# coreV_01.net
KiCad netlist of a schematic drawn in EAGLE
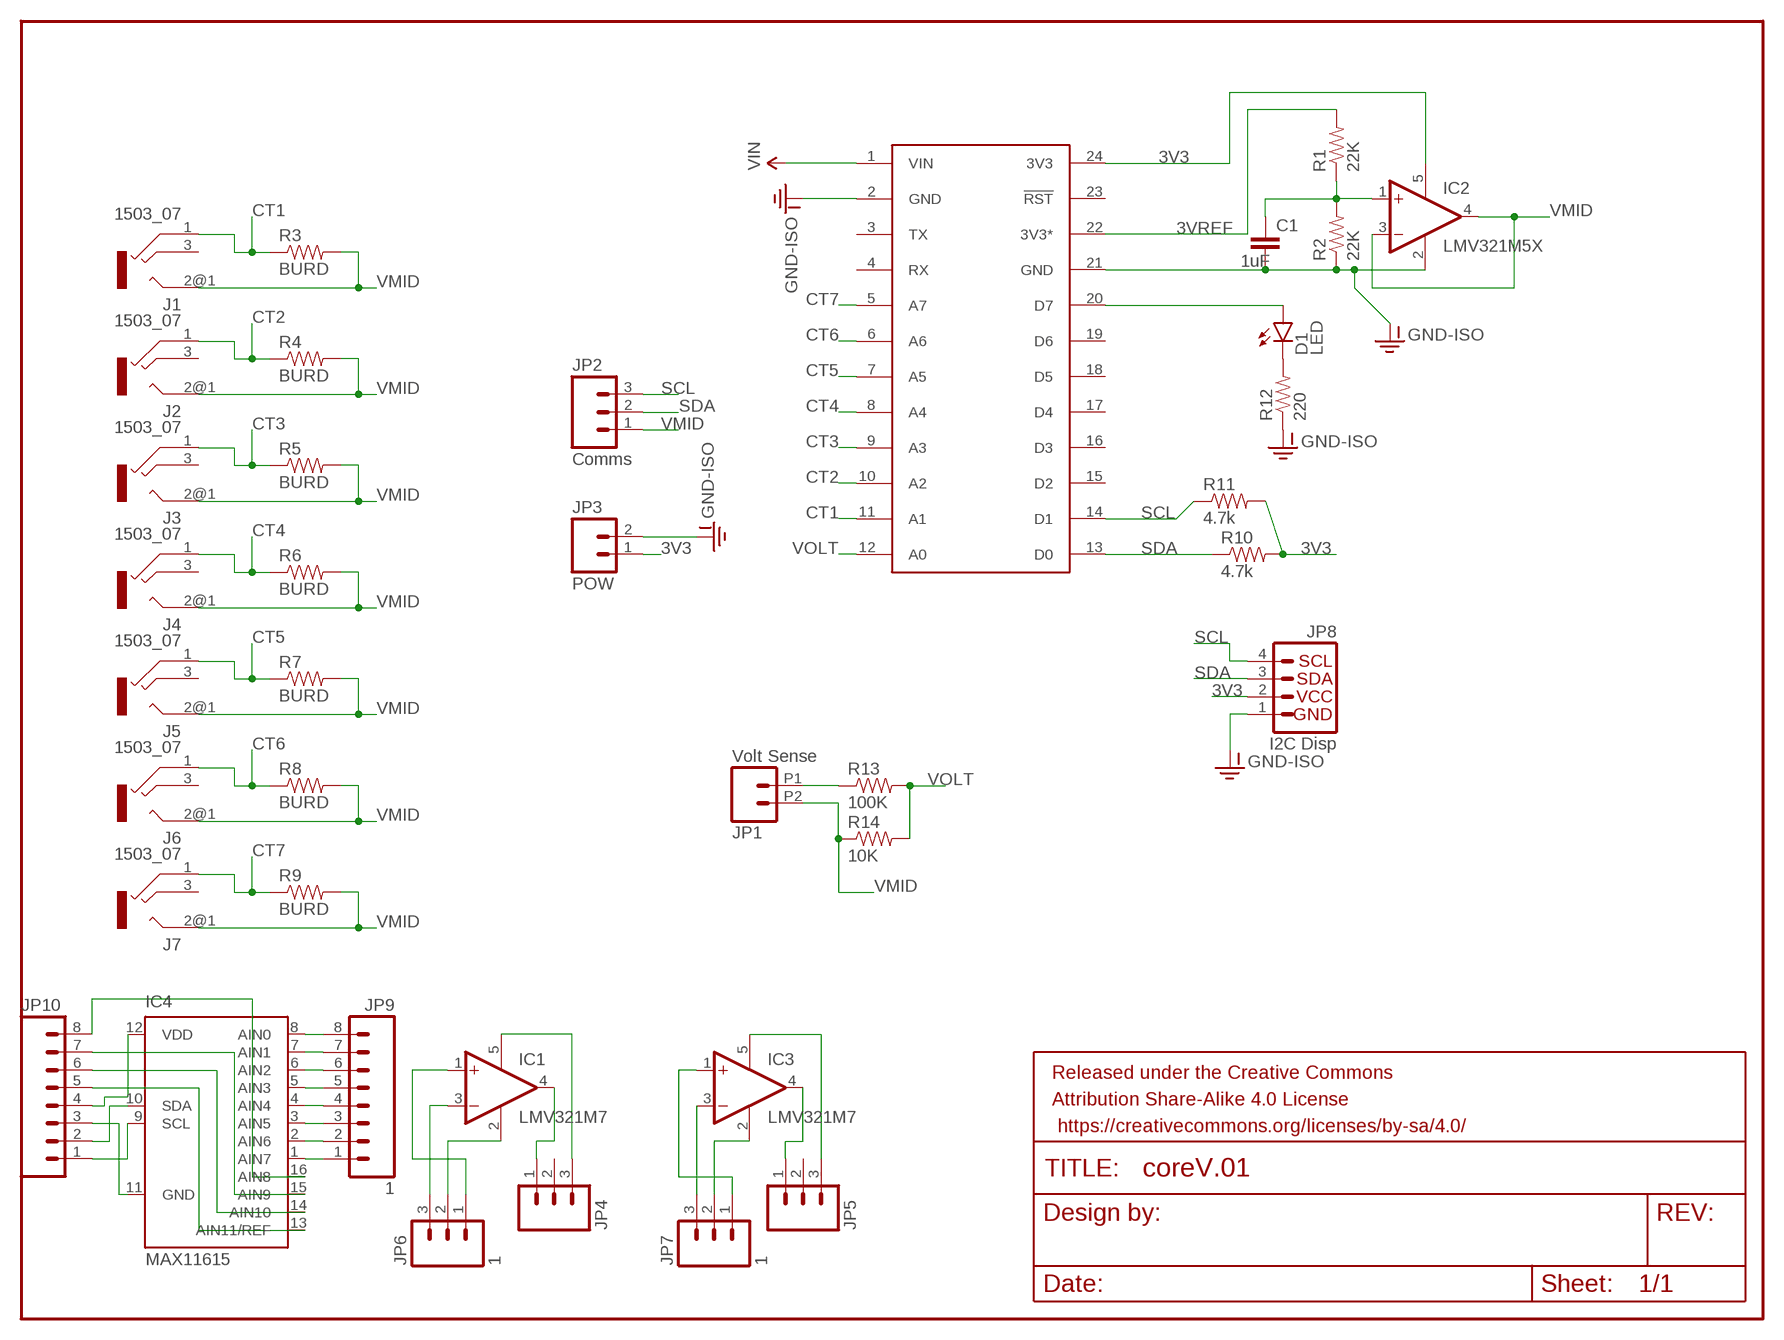
[diagram p0: schematic, sheet 1]

(export (version "E")
  (design (tool "Eeschema 10.0.6"))
  (components
    (comp (ref "C1")
      (value "1uF")
      (footprint "eagle-import:CAP-PTH-SMALL")
      (libsource (lib "eagle-import") (part "CAPPTH"))
    )
    (comp (ref "D1")
      (value "LED")
      (footprint "eagle-import:LED3MM")
      (libsource (lib "eagle-import") (part "LED3MM"))
    )
    (comp (ref "FRAME1")
      (value "emonCore")
      (footprint "eagle-import:CREATIVE_COMMONS")
      (fields (field (name "DESIGNER") "NAME"))
      (libsource (lib "eagle-import") (part "FRAME-LETTER"))
    )
    (comp (ref "IC1")
      (value "LMV321M7")
      (footprint "eagle-import:SC70-5L")
      (libsource (lib "eagle-import") (part "LMV321?M7"))
    )
    (comp (ref "IC2")
      (value "LMV321M5X")
      (footprint "eagle-import:SOT23-5")
      (libsource (lib "eagle-import") (part "LMV321?M5X"))
    )
    (comp (ref "IC3")
      (value "LMV321M7")
      (footprint "eagle-import:SC70-5L")
      (libsource (lib "eagle-import") (part "LMV321?M7"))
    )
    (comp (ref "IC4")
      (value "MAX11615")
      (footprint "eagle-import:QSOP16")
      (fields (field (name "MF") "MAXIM") (field (name "MPN") "MAX1039AEEE+"))
      (libsource (lib "eagle-import") (part "MAX1039"))
    )
    (comp (ref "J1")
      (value "1503_07")
      (footprint "eagle-import:1503_07")
      (libsource (lib "eagle-import") (part "1503_?07"))
    )
    (comp (ref "J2")
      (value "1503_07")
      (footprint "eagle-import:1503_07")
      (libsource (lib "eagle-import") (part "1503_?07"))
    )
    (comp (ref "J3")
      (value "1503_07")
      (footprint "eagle-import:1503_07")
      (libsource (lib "eagle-import") (part "1503_?07"))
    )
    (comp (ref "J4")
      (value "1503_07")
      (footprint "eagle-import:1503_07")
      (libsource (lib "eagle-import") (part "1503_?07"))
    )
    (comp (ref "J5")
      (value "1503_07")
      (footprint "eagle-import:1503_07")
      (libsource (lib "eagle-import") (part "1503_?07"))
    )
    (comp (ref "J6")
      (value "1503_07")
      (footprint "eagle-import:1503_07")
      (libsource (lib "eagle-import") (part "1503_?07"))
    )
    (comp (ref "J7")
      (value "1503_07")
      (footprint "eagle-import:1503_07")
      (libsource (lib "eagle-import") (part "1503_?07"))
    )
    (comp (ref "JP1")
      (value "Volt Sense")
      (footprint "eagle-import:1X02_2.54_SCREWTERM")
      (libsource (lib "eagle-import") (part "M022.54MM_SCREWTERM"))
    )
    (comp (ref "JP2")
      (value "Comms")
      (footprint "eagle-import:1X03")
      (libsource (lib "eagle-import") (part "M03PTH"))
    )
    (comp (ref "JP3")
      (value "POW")
      (footprint "eagle-import:1X02")
      (libsource (lib "eagle-import") (part "M02PTH"))
    )
    (comp (ref "JP4")
      (value "M03PTH")
      (footprint "eagle-import:1X03")
      (libsource (lib "eagle-import") (part "M03PTH"))
    )
    (comp (ref "JP5")
      (value "M03PTH")
      (footprint "eagle-import:1X03")
      (libsource (lib "eagle-import") (part "M03PTH"))
    )
    (comp (ref "JP6")
      (value "1")
      (footprint "eagle-import:1X03")
      (libsource (lib "eagle-import") (part "M03PTH"))
    )
    (comp (ref "JP7")
      (value "1")
      (footprint "eagle-import:1X03")
      (libsource (lib "eagle-import") (part "M03PTH"))
    )
    (comp (ref "JP8")
      (value "I2C Disp")
      (footprint "eagle-import:1X04")
      (libsource (lib "eagle-import") (part "I2C_STANDARD"))
    )
    (comp (ref "JP9")
      (value "1")
      (footprint "eagle-import:1X08")
      (libsource (lib "eagle-import") (part "M08SILK_FEMALE_PTH"))
    )
    (comp (ref "JP10")
      (value "M08SILK_FEMALE_PTH")
      (footprint "eagle-import:1X08")
      (libsource (lib "eagle-import") (part "M08SILK_FEMALE_PTH"))
    )
    (comp (ref "R1")
      (value "22K")
      (footprint "eagle-import:AXIAL-0.3")
      (libsource (lib "eagle-import") (part "RESISTORAXIAL-0.3"))
    )
    (comp (ref "R2")
      (value "22K")
      (footprint "eagle-import:AXIAL-0.3")
      (libsource (lib "eagle-import") (part "RESISTORAXIAL-0.3"))
    )
    (comp (ref "R3")
      (value "BURD")
      (footprint "eagle-import:AXIAL-0.3")
      (libsource (lib "eagle-import") (part "RESISTORAXIAL-0.3"))
    )
    (comp (ref "R4")
      (value "BURD")
      (footprint "eagle-import:AXIAL-0.3")
      (libsource (lib "eagle-import") (part "RESISTORAXIAL-0.3"))
    )
    (comp (ref "R5")
      (value "BURD")
      (footprint "eagle-import:AXIAL-0.3")
      (libsource (lib "eagle-import") (part "RESISTORAXIAL-0.3"))
    )
    (comp (ref "R6")
      (value "BURD")
      (footprint "eagle-import:AXIAL-0.3")
      (libsource (lib "eagle-import") (part "RESISTORAXIAL-0.3"))
    )
    (comp (ref "R7")
      (value "BURD")
      (footprint "eagle-import:AXIAL-0.3")
      (libsource (lib "eagle-import") (part "RESISTORAXIAL-0.3"))
    )
    (comp (ref "R8")
      (value "BURD")
      (footprint "eagle-import:AXIAL-0.3")
      (libsource (lib "eagle-import") (part "RESISTORAXIAL-0.3"))
    )
    (comp (ref "R9")
      (value "BURD")
      (footprint "eagle-import:AXIAL-0.3")
      (libsource (lib "eagle-import") (part "RESISTORAXIAL-0.3"))
    )
    (comp (ref "R10")
      (value "4.7k")
      (footprint "eagle-import:AXIAL-0.3")
      (libsource (lib "eagle-import") (part "RESISTORAXIAL-0.3"))
    )
    (comp (ref "R11")
      (value "4.7k")
      (footprint "eagle-import:AXIAL-0.3")
      (libsource (lib "eagle-import") (part "RESISTORAXIAL-0.3"))
    )
    (comp (ref "R12")
      (value "220")
      (footprint "eagle-import:AXIAL-0.3")
      (libsource (lib "eagle-import") (part "RESISTORAXIAL-0.3"))
    )
    (comp (ref "R13")
      (value "100K")
      (footprint "eagle-import:AXIAL-0.3")
      (libsource (lib "eagle-import") (part "RESISTORAXIAL-0.3"))
    )
    (comp (ref "R14")
      (value "10K")
      (footprint "eagle-import:AXIAL-0.3")
      (libsource (lib "eagle-import") (part "RESISTORAXIAL-0.3"))
    )
    (comp (ref "U$1")
      (value "SPARK_CORE")
      (footprint "eagle-import:SPARK_CORE")
      (libsource (lib "eagle-import") (part "SPARK_CORECORE"))
    )
  )
  (nets
    (net (code "1") (name "/3V3") (class "Default")
      (node (ref "IC2") (pin "5") (pinfunction "V+_5") (pintype "power_in"))
      (node (ref "JP3") (pin "1") (pinfunction "1_1") (pintype "passive"))
      (node (ref "JP8") (pin "2") (pinfunction "2_2") (pintype "passive"))
      (node (ref "R10") (pin "P$2") (pinfunction "2_P$2") (pintype "passive"))
      (node (ref "R11") (pin "P$2") (pinfunction "2_P$2") (pintype "passive"))
      (node (ref "U$1") (pin "24") (pinfunction "3V3_24") (pintype "power_in"))
    )
    (net (code "2") (name "/3VREF") (class "Default")
      (node (ref "R1") (pin "P$2") (pinfunction "2_P$2") (pintype "passive"))
      (node (ref "U$1") (pin "22") (pinfunction "3V3*_22") (pintype "power_in"))
    )
    (net (code "3") (name "/CT1") (class "Default")
      (node (ref "J1") (pin "1") (pinfunction "1_1") (pintype "passive"))
      (node (ref "R3") (pin "P$1") (pinfunction "1_P$1") (pintype "passive"))
      (node (ref "U$1") (pin "11") (pinfunction "A1_11") (pintype "bidirectional"))
    )
    (net (code "4") (name "/CT2") (class "Default")
      (node (ref "J2") (pin "1") (pinfunction "1_1") (pintype "passive"))
      (node (ref "R4") (pin "P$1") (pinfunction "1_P$1") (pintype "passive"))
      (node (ref "U$1") (pin "10") (pinfunction "A2_10") (pintype "bidirectional"))
    )
    (net (code "5") (name "/CT3") (class "Default")
      (node (ref "J3") (pin "1") (pinfunction "1_1") (pintype "passive"))
      (node (ref "R5") (pin "P$1") (pinfunction "1_P$1") (pintype "passive"))
      (node (ref "U$1") (pin "9") (pinfunction "A3_9") (pintype "bidirectional"))
    )
    (net (code "6") (name "/CT4") (class "Default")
      (node (ref "J4") (pin "1") (pinfunction "1_1") (pintype "passive"))
      (node (ref "R6") (pin "P$1") (pinfunction "1_P$1") (pintype "passive"))
      (node (ref "U$1") (pin "8") (pinfunction "A4_8") (pintype "bidirectional"))
    )
    (net (code "7") (name "/CT5") (class "Default")
      (node (ref "J5") (pin "1") (pinfunction "1_1") (pintype "passive"))
      (node (ref "R7") (pin "P$1") (pinfunction "1_P$1") (pintype "passive"))
      (node (ref "U$1") (pin "7") (pinfunction "A5_7") (pintype "bidirectional"))
    )
    (net (code "8") (name "/CT6") (class "Default")
      (node (ref "J6") (pin "1") (pinfunction "1_1") (pintype "passive"))
      (node (ref "R8") (pin "P$1") (pinfunction "1_P$1") (pintype "passive"))
      (node (ref "U$1") (pin "6") (pinfunction "A6_6") (pintype "bidirectional"))
    )
    (net (code "9") (name "/CT7") (class "Default")
      (node (ref "J7") (pin "1") (pinfunction "1_1") (pintype "passive"))
      (node (ref "R9") (pin "P$1") (pinfunction "1_P$1") (pintype "passive"))
      (node (ref "U$1") (pin "5") (pinfunction "A7_5") (pintype "bidirectional"))
    )
    (net (code "10") (name "/SCL") (class "Default")
      (node (ref "JP2") (pin "3") (pinfunction "3_3") (pintype "passive"))
      (node (ref "JP8") (pin "4") (pinfunction "4_4") (pintype "passive"))
      (node (ref "R11") (pin "P$1") (pinfunction "1_P$1") (pintype "passive"))
      (node (ref "U$1") (pin "14") (pinfunction "D1_14") (pintype "bidirectional"))
    )
    (net (code "11") (name "/SDA") (class "Default")
      (node (ref "JP2") (pin "2") (pinfunction "2_2") (pintype "passive"))
      (node (ref "JP8") (pin "3") (pinfunction "3_3") (pintype "passive"))
      (node (ref "R10") (pin "P$1") (pinfunction "1_P$1") (pintype "passive"))
      (node (ref "U$1") (pin "13") (pinfunction "D0_13") (pintype "bidirectional"))
    )
    (net (code "12") (name "/VMID") (class "Default")
      (node (ref "IC2") (pin "3") (pinfunction "-IN_3") (pintype "input"))
      (node (ref "IC2") (pin "4") (pinfunction "OUT_4") (pintype "output"))
      (node (ref "J1") (pin "2@1") (pinfunction "2_2@1") (pintype "passive"))
      (node (ref "J2") (pin "2@1") (pinfunction "2_2@1") (pintype "passive"))
      (node (ref "J3") (pin "2@1") (pinfunction "2_2@1") (pintype "passive"))
      (node (ref "J4") (pin "2@1") (pinfunction "2_2@1") (pintype "passive"))
      (node (ref "J5") (pin "2@1") (pinfunction "2_2@1") (pintype "passive"))
      (node (ref "J6") (pin "2@1") (pinfunction "2_2@1") (pintype "passive"))
      (node (ref "J7") (pin "2@1") (pinfunction "2_2@1") (pintype "passive"))
      (node (ref "JP1") (pin "P2") (pinfunction "2_P2") (pintype "passive"))
      (node (ref "JP2") (pin "1") (pinfunction "1_1") (pintype "passive"))
      (node (ref "R14") (pin "P$1") (pinfunction "1_P$1") (pintype "passive"))
      (node (ref "R3") (pin "P$2") (pinfunction "2_P$2") (pintype "passive"))
      (node (ref "R4") (pin "P$2") (pinfunction "2_P$2") (pintype "passive"))
      (node (ref "R5") (pin "P$2") (pinfunction "2_P$2") (pintype "passive"))
      (node (ref "R6") (pin "P$2") (pinfunction "2_P$2") (pintype "passive"))
      (node (ref "R7") (pin "P$2") (pinfunction "2_P$2") (pintype "passive"))
      (node (ref "R8") (pin "P$2") (pinfunction "2_P$2") (pintype "passive"))
      (node (ref "R9") (pin "P$2") (pinfunction "2_P$2") (pintype "passive"))
    )
    (net (code "13") (name "/VOLT") (class "Default")
      (node (ref "R13") (pin "P$2") (pinfunction "2_P$2") (pintype "passive"))
      (node (ref "R14") (pin "P$2") (pinfunction "2_P$2") (pintype "passive"))
      (node (ref "U$1") (pin "12") (pinfunction "A0_12") (pintype "bidirectional"))
    )
    (net (code "14") (name "GND-ISO") (class "Default")
      (node (ref "C1") (pin "2") (pinfunction "2_2") (pintype "passive"))
      (node (ref "IC2") (pin "2") (pinfunction "V-_2") (pintype "power_in"))
      (node (ref "JP3") (pin "2") (pinfunction "2_2") (pintype "passive"))
      (node (ref "JP8") (pin "1") (pinfunction "1_1") (pintype "passive"))
      (node (ref "R12") (pin "P$1") (pinfunction "1_P$1") (pintype "passive"))
      (node (ref "R2") (pin "P$1") (pinfunction "1_P$1") (pintype "passive"))
      (node (ref "U$1") (pin "2") (pinfunction "GND_2") (pintype "power_in"))
      (node (ref "U$1") (pin "21") (pinfunction "GND_21") (pintype "power_in"))
    )
    (net (code "15") (name "Net-(D1-C)") (class "Default")
      (node (ref "D1") (pin "K") (pinfunction "C_K") (pintype "passive"))
      (node (ref "R12") (pin "P$2") (pinfunction "2_P$2") (pintype "passive"))
    )
    (net (code "16") (name "Net-(IC1-+IN)") (class "Default")
      (node (ref "IC1") (pin "1") (pinfunction "+IN_1") (pintype "input"))
      (node (ref "JP6") (pin "1") (pinfunction "1_1") (pintype "passive"))
    )
    (net (code "17") (name "Net-(IC1--IN)") (class "Default")
      (node (ref "IC1") (pin "3") (pinfunction "-IN_3") (pintype "input"))
      (node (ref "JP6") (pin "3") (pinfunction "3_3") (pintype "passive"))
    )
    (net (code "18") (name "Net-(IC1-OUT)") (class "Default")
      (node (ref "IC1") (pin "4") (pinfunction "OUT_4") (pintype "output"))
      (node (ref "JP4") (pin "1") (pinfunction "1_1") (pintype "passive"))
    )
    (net (code "19") (name "Net-(IC1-V+)") (class "Default")
      (node (ref "IC1") (pin "5") (pinfunction "V+_5") (pintype "power_in"))
      (node (ref "JP4") (pin "3") (pinfunction "3_3") (pintype "passive"))
    )
    (net (code "20") (name "Net-(IC1-V-)") (class "Default")
      (node (ref "IC1") (pin "2") (pinfunction "V-_2") (pintype "power_in"))
      (node (ref "JP6") (pin "2") (pinfunction "2_2") (pintype "passive"))
    )
    (net (code "21") (name "Net-(IC2-+IN)") (class "Default")
      (node (ref "C1") (pin "1") (pinfunction "1_1") (pintype "passive"))
      (node (ref "IC2") (pin "1") (pinfunction "+IN_1") (pintype "input"))
      (node (ref "R1") (pin "P$1") (pinfunction "1_P$1") (pintype "passive"))
      (node (ref "R2") (pin "P$2") (pinfunction "2_P$2") (pintype "passive"))
    )
    (net (code "22") (name "Net-(IC3-+IN)") (class "Default")
      (node (ref "IC3") (pin "1") (pinfunction "+IN_1") (pintype "input"))
      (node (ref "JP7") (pin "1") (pinfunction "1_1") (pintype "passive"))
    )
    (net (code "23") (name "Net-(IC3--IN)") (class "Default")
      (node (ref "IC3") (pin "3") (pinfunction "-IN_3") (pintype "input"))
      (node (ref "JP7") (pin "3") (pinfunction "3_3") (pintype "passive"))
    )
    (net (code "24") (name "Net-(IC3-OUT)") (class "Default")
      (node (ref "IC3") (pin "4") (pinfunction "OUT_4") (pintype "output"))
      (node (ref "JP5") (pin "1") (pinfunction "1_1") (pintype "passive"))
    )
    (net (code "25") (name "Net-(IC3-V+)") (class "Default")
      (node (ref "IC3") (pin "5") (pinfunction "V+_5") (pintype "power_in"))
      (node (ref "JP5") (pin "3") (pinfunction "3_3") (pintype "passive"))
    )
    (net (code "26") (name "Net-(IC3-V-)") (class "Default")
      (node (ref "IC3") (pin "2") (pinfunction "V-_2") (pintype "power_in"))
      (node (ref "JP7") (pin "2") (pinfunction "2_2") (pintype "passive"))
    )
    (net (code "27") (name "Net-(IC4-AIN0)") (class "Default")
      (node (ref "IC4") (pin "8") (pinfunction "AIN0_8") (pintype "input"))
      (node (ref "JP9") (pin "8") (pinfunction "8_8") (pintype "passive"))
    )
    (net (code "28") (name "Net-(IC4-AIN1)") (class "Default")
      (node (ref "IC4") (pin "7") (pinfunction "AIN1_7") (pintype "input"))
      (node (ref "JP9") (pin "7") (pinfunction "7_7") (pintype "passive"))
    )
    (net (code "29") (name "Net-(IC4-AIN2)") (class "Default")
      (node (ref "IC4") (pin "6") (pinfunction "AIN2_6") (pintype "input"))
      (node (ref "JP9") (pin "6") (pinfunction "6_6") (pintype "passive"))
    )
    (net (code "30") (name "Net-(IC4-AIN3)") (class "Default")
      (node (ref "IC4") (pin "5") (pinfunction "AIN3_5") (pintype "input"))
      (node (ref "JP9") (pin "5") (pinfunction "5_5") (pintype "passive"))
    )
    (net (code "31") (name "Net-(IC4-AIN4)") (class "Default")
      (node (ref "IC4") (pin "4") (pinfunction "AIN4_4") (pintype "input"))
      (node (ref "JP9") (pin "4") (pinfunction "4_4") (pintype "passive"))
    )
    (net (code "32") (name "Net-(IC4-AIN5)") (class "Default")
      (node (ref "IC4") (pin "3") (pinfunction "AIN5_3") (pintype "input"))
      (node (ref "JP9") (pin "3") (pinfunction "3_3") (pintype "passive"))
    )
    (net (code "33") (name "Net-(IC4-AIN6)") (class "Default")
      (node (ref "IC4") (pin "2") (pinfunction "AIN6_2") (pintype "input"))
      (node (ref "JP9") (pin "2") (pinfunction "2_2") (pintype "passive"))
    )
    (net (code "34") (name "Net-(IC4-AIN7)") (class "Default")
      (node (ref "IC4") (pin "1") (pinfunction "AIN7_1") (pintype "input"))
      (node (ref "JP9") (pin "1") (pinfunction "1_1") (pintype "passive"))
    )
    (net (code "35") (name "Net-(IC4-AIN8)") (class "Default")
      (node (ref "IC4") (pin "16") (pinfunction "AIN8_16") (pintype "input"))
      (node (ref "JP10") (pin "8") (pinfunction "8_8") (pintype "passive"))
    )
    (net (code "36") (name "Net-(IC4-AIN9)") (class "Default")
      (node (ref "IC4") (pin "15") (pinfunction "AIN9_15") (pintype "input"))
      (node (ref "JP10") (pin "7") (pinfunction "7_7") (pintype "passive"))
    )
    (net (code "37") (name "Net-(IC4-AIN10)") (class "Default")
      (node (ref "IC4") (pin "14") (pinfunction "AIN10_14") (pintype "input"))
      (node (ref "JP10") (pin "6") (pinfunction "6_6") (pintype "passive"))
    )
    (net (code "38") (name "Net-(IC4-AIN11{slash}REF)") (class "Default")
      (node (ref "IC4") (pin "13") (pinfunction "AIN11/REF_13") (pintype "input"))
      (node (ref "JP10") (pin "5") (pinfunction "5_5") (pintype "passive"))
    )
    (net (code "39") (name "Net-(IC4-GND)") (class "Default")
      (node (ref "IC4") (pin "11") (pinfunction "GND_11") (pintype "power_in"))
      (node (ref "JP10") (pin "3") (pinfunction "3_3") (pintype "passive"))
    )
    (net (code "40") (name "Net-(IC4-SCL)") (class "Default")
      (node (ref "IC4") (pin "9") (pinfunction "SCL_9") (pintype "input"))
      (node (ref "JP10") (pin "1") (pinfunction "1_1") (pintype "passive"))
    )
    (net (code "41") (name "Net-(IC4-SDA)") (class "Default")
      (node (ref "IC4") (pin "10") (pinfunction "SDA_10") (pintype "input"))
      (node (ref "JP10") (pin "2") (pinfunction "2_2") (pintype "passive"))
    )
    (net (code "42") (name "Net-(IC4-VDD)") (class "Default")
      (node (ref "IC4") (pin "12") (pinfunction "VDD_12") (pintype "power_in"))
      (node (ref "JP10") (pin "4") (pinfunction "4_4") (pintype "passive"))
    )
    (net (code "43") (name "Net-(JP1-1)") (class "Default")
      (node (ref "JP1") (pin "P1") (pinfunction "1_P1") (pintype "passive"))
      (node (ref "R13") (pin "P$1") (pinfunction "1_P$1") (pintype "passive"))
    )
    (net (code "44") (name "Net-(U$1-D7)") (class "Default")
      (node (ref "D1") (pin "A") (pinfunction "A_A") (pintype "passive"))
      (node (ref "U$1") (pin "20") (pinfunction "D7_20") (pintype "bidirectional"))
    )
    (net (code "45") (name "VIN") (class "Default")
      (node (ref "U$1") (pin "1") (pinfunction "VIN_1") (pintype "power_in"))
    )
    (net (code "46") (name "unconnected-(J1-2-Pad2@2)") (class "Default")
      (node (ref "J1") (pin "2@2") (pinfunction "2_2@2") (pintype "passive"))
    )
    (net (code "47") (name "unconnected-(J1-Pad3)") (class "Default")
      (node (ref "J1") (pin "3") (pinfunction "3_3") (pintype "passive"))
    )
    (net (code "48") (name "unconnected-(J2-2-Pad2@2)") (class "Default")
      (node (ref "J2") (pin "2@2") (pinfunction "2_2@2") (pintype "passive"))
    )
    (net (code "49") (name "unconnected-(J2-Pad3)") (class "Default")
      (node (ref "J2") (pin "3") (pinfunction "3_3") (pintype "passive"))
    )
    (net (code "50") (name "unconnected-(J3-2-Pad2@2)") (class "Default")
      (node (ref "J3") (pin "2@2") (pinfunction "2_2@2") (pintype "passive"))
    )
    (net (code "51") (name "unconnected-(J3-Pad3)") (class "Default")
      (node (ref "J3") (pin "3") (pinfunction "3_3") (pintype "passive"))
    )
    (net (code "52") (name "unconnected-(J4-2-Pad2@2)") (class "Default")
      (node (ref "J4") (pin "2@2") (pinfunction "2_2@2") (pintype "passive"))
    )
    (net (code "53") (name "unconnected-(J4-Pad3)") (class "Default")
      (node (ref "J4") (pin "3") (pinfunction "3_3") (pintype "passive"))
    )
    (net (code "54") (name "unconnected-(J5-2-Pad2@2)") (class "Default")
      (node (ref "J5") (pin "2@2") (pinfunction "2_2@2") (pintype "passive"))
    )
    (net (code "55") (name "unconnected-(J5-Pad3)") (class "Default")
      (node (ref "J5") (pin "3") (pinfunction "3_3") (pintype "passive"))
    )
    (net (code "56") (name "unconnected-(J6-2-Pad2@2)") (class "Default")
      (node (ref "J6") (pin "2@2") (pinfunction "2_2@2") (pintype "passive"))
    )
    (net (code "57") (name "unconnected-(J6-Pad3)") (class "Default")
      (node (ref "J6") (pin "3") (pinfunction "3_3") (pintype "passive"))
    )
    (net (code "58") (name "unconnected-(J7-2-Pad2@2)") (class "Default")
      (node (ref "J7") (pin "2@2") (pinfunction "2_2@2") (pintype "passive"))
    )
    (net (code "59") (name "unconnected-(J7-Pad3)") (class "Default")
      (node (ref "J7") (pin "3") (pinfunction "3_3") (pintype "passive"))
    )
    (net (code "60") (name "unconnected-(JP4-Pad2)") (class "Default")
      (node (ref "JP4") (pin "2") (pinfunction "2_2") (pintype "passive"))
    )
    (net (code "61") (name "unconnected-(JP5-Pad2)") (class "Default")
      (node (ref "JP5") (pin "2") (pinfunction "2_2") (pintype "passive"))
    )
    (net (code "62") (name "unconnected-(U$1-D2-Pad15)") (class "Default")
      (node (ref "U$1") (pin "15") (pinfunction "D2_15") (pintype "bidirectional"))
    )
    (net (code "63") (name "unconnected-(U$1-D3-Pad16)") (class "Default")
      (node (ref "U$1") (pin "16") (pinfunction "D3_16") (pintype "bidirectional"))
    )
    (net (code "64") (name "unconnected-(U$1-D4-Pad17)") (class "Default")
      (node (ref "U$1") (pin "17") (pinfunction "D4_17") (pintype "bidirectional"))
    )
    (net (code "65") (name "unconnected-(U$1-D5-Pad18)") (class "Default")
      (node (ref "U$1") (pin "18") (pinfunction "D5_18") (pintype "bidirectional"))
    )
    (net (code "66") (name "unconnected-(U$1-D6-Pad19)") (class "Default")
      (node (ref "U$1") (pin "19") (pinfunction "D6_19") (pintype "bidirectional"))
    )
    (net (code "67") (name "unconnected-(U$1-RX-Pad4)") (class "Default")
      (node (ref "U$1") (pin "4") (pinfunction "RX_4") (pintype "bidirectional"))
    )
    (net (code "68") (name "unconnected-(U$1-TX-Pad3)") (class "Default")
      (node (ref "U$1") (pin "3") (pinfunction "TX_3") (pintype "bidirectional"))
    )
    (net (code "69") (name "unconnected-(U$1-~{RST}-Pad23)") (class "Default")
      (node (ref "U$1") (pin "23") (pinfunction "~{RST}_23") (pintype "bidirectional"))
    )
  )
)
